# VOX_V847.net
KiCad netlist of a schematic drawn in EAGLE
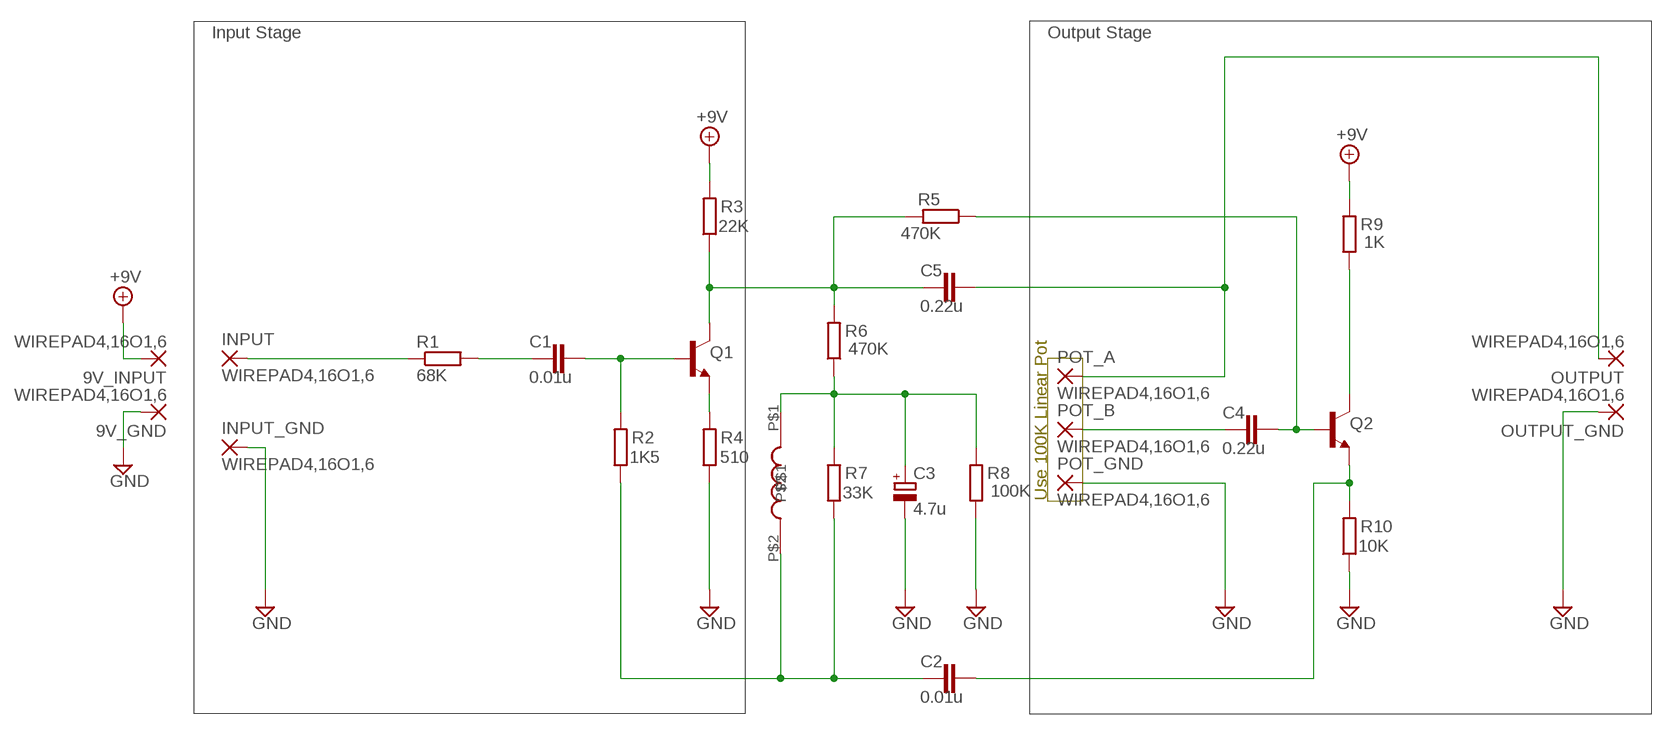
[diagram p0: schematic, sheet 1]

(export (version "E")
  (design (tool "Eeschema 10.0.6"))
  (components
    (comp (ref "9V_GND")
      (value "WIREPAD4,16O1,6")
      (footprint "eagle-import:4,16O1,6")
      (libsource (lib "eagle-import") (part "WIREPAD4,16O1,6"))
    )
    (comp (ref "9V_INPUT")
      (value "WIREPAD4,16O1,6")
      (footprint "eagle-import:4,16O1,6")
      (libsource (lib "eagle-import") (part "WIREPAD4,16O1,6"))
    )
    (comp (ref "C1")
      (value "0.01u")
      (footprint "eagle-import:C050-024X044")
      (libsource (lib "eagle-import") (part "C-EU050-024X044"))
    )
    (comp (ref "C2")
      (value "0.01u")
      (footprint "eagle-import:C050-024X044")
      (libsource (lib "eagle-import") (part "C-EU050-024X044"))
    )
    (comp (ref "C3")
      (value "4.7u")
      (footprint "eagle-import:E5-5")
      (libsource (lib "eagle-import") (part "CPOL-EUE5-5"))
    )
    (comp (ref "C4")
      (value "0.22u")
      (footprint "eagle-import:C075-042X103")
      (libsource (lib "eagle-import") (part "C-EU075-042X103"))
    )
    (comp (ref "C5")
      (value "0.22u")
      (footprint "eagle-import:C050-024X044")
      (libsource (lib "eagle-import") (part "C-EU050-024X044"))
    )
    (comp (ref "INPUT")
      (value "WIREPAD4,16O1,6")
      (footprint "eagle-import:4,16O1,6")
      (libsource (lib "eagle-import") (part "WIREPAD4,16O1,6"))
    )
    (comp (ref "INPUT_GND")
      (value "WIREPAD4,16O1,6")
      (footprint "eagle-import:4,16O1,6")
      (libsource (lib "eagle-import") (part "WIREPAD4,16O1,6"))
    )
    (comp (ref "OUTPUT")
      (value "WIREPAD4,16O1,6")
      (footprint "eagle-import:4,16O1,6")
      (libsource (lib "eagle-import") (part "WIREPAD4,16O1,6"))
    )
    (comp (ref "OUTPUT_GND")
      (value "WIREPAD4,16O1,6")
      (footprint "eagle-import:4,16O1,6")
      (libsource (lib "eagle-import") (part "WIREPAD4,16O1,6"))
    )
    (comp (ref "POT_A")
      (value "WIREPAD4,16O1,6")
      (footprint "eagle-import:4,16O1,6")
      (libsource (lib "eagle-import") (part "WIREPAD4,16O1,6"))
    )
    (comp (ref "POT_B")
      (value "WIREPAD4,16O1,6")
      (footprint "eagle-import:4,16O1,6")
      (libsource (lib "eagle-import") (part "WIREPAD4,16O1,6"))
    )
    (comp (ref "POT_GND")
      (value "WIREPAD4,16O1,6")
      (footprint "eagle-import:4,16O1,6")
      (libsource (lib "eagle-import") (part "WIREPAD4,16O1,6"))
    )
    (comp (ref "Q1")
      (value "MPSA18-NPN-TO92-EBC")
      (footprint "eagle-import:TO92-EBC")
      (libsource (lib "eagle-import") (part "-NPN-TO92-EBCMPSA18"))
    )
    (comp (ref "Q2")
      (value "MPSA18-NPN-TO92-EBC")
      (footprint "eagle-import:TO92-EBC")
      (libsource (lib "eagle-import") (part "-NPN-TO92-EBCMPSA18"))
    )
    (comp (ref "R1")
      (value "68K")
      (footprint "eagle-import:0207_7")
      (libsource (lib "eagle-import") (part "R-EU_0207/7"))
    )
    (comp (ref "R2")
      (value "1K5")
      (footprint "eagle-import:0207_12")
      (libsource (lib "eagle-import") (part "R-EU_0207/12"))
    )
    (comp (ref "R3")
      (value "22K")
      (footprint "eagle-import:0207_7")
      (libsource (lib "eagle-import") (part "R-EU_0207/7"))
    )
    (comp (ref "R4")
      (value "510")
      (footprint "eagle-import:0207_10")
      (libsource (lib "eagle-import") (part "R-EU_0207/10"))
    )
    (comp (ref "R5")
      (value "470K")
      (footprint "eagle-import:0207_7")
      (libsource (lib "eagle-import") (part "R-EU_0207/7"))
    )
    (comp (ref "R6")
      (value "470K")
      (footprint "eagle-import:0207_7")
      (libsource (lib "eagle-import") (part "R-EU_0207/7"))
    )
    (comp (ref "R7")
      (value "33K")
      (footprint "eagle-import:0207_7")
      (libsource (lib "eagle-import") (part "R-EU_0207/7"))
    )
    (comp (ref "R8")
      (value "100K")
      (footprint "eagle-import:0207_7")
      (libsource (lib "eagle-import") (part "R-EU_0207/7"))
    )
    (comp (ref "R9")
      (value "1K")
      (footprint "eagle-import:0207_12")
      (libsource (lib "eagle-import") (part "R-EU_0207/12"))
    )
    (comp (ref "R10")
      (value "10K")
      (footprint "eagle-import:0207_7")
      (libsource (lib "eagle-import") (part "R-EU_0207/7"))
    )
    (comp (ref "U$1")
      (value "FL01Y")
      (footprint "eagle-import:FL01Y")
      (libsource (lib "eagle-import") (part "FL01Y"))
    )
  )
  (nets
    (net (code "1") (name "+9V") (class "Default")
      (node (ref "9V_INPUT") (pin "1") (pinfunction "P_1") (pintype "passive"))
      (node (ref "R3") (pin "2") (pinfunction "2_2") (pintype "passive"))
      (node (ref "R9") (pin "2") (pinfunction "2_2") (pintype "passive"))
    )
    (net (code "2") (name "GND") (class "Default")
      (node (ref "9V_GND") (pin "1") (pinfunction "P_1") (pintype "passive"))
      (node (ref "C3") (pin "-") (pinfunction "-_-") (pintype "passive"))
      (node (ref "INPUT_GND") (pin "1") (pinfunction "P_1") (pintype "passive"))
      (node (ref "OUTPUT_GND") (pin "1") (pinfunction "P_1") (pintype "passive"))
      (node (ref "POT_GND") (pin "1") (pinfunction "P_1") (pintype "passive"))
      (node (ref "R10") (pin "1") (pinfunction "1_1") (pintype "passive"))
      (node (ref "R4") (pin "1") (pinfunction "1_1") (pintype "passive"))
      (node (ref "R8") (pin "1") (pinfunction "1_1") (pintype "passive"))
    )
    (net (code "3") (name "Net-(C1-Pad1)") (class "Default")
      (node (ref "C1") (pin "1") (pinfunction "1_1") (pintype "passive"))
      (node (ref "R1") (pin "2") (pinfunction "2_2") (pintype "passive"))
    )
    (net (code "4") (name "Net-(C1-Pad2)") (class "Default")
      (node (ref "C1") (pin "2") (pinfunction "2_2") (pintype "passive"))
      (node (ref "Q1") (pin "B") (pinfunction "B_B") (pintype "passive"))
      (node (ref "R2") (pin "2") (pinfunction "2_2") (pintype "passive"))
    )
    (net (code "5") (name "Net-(C2-Pad1)") (class "Default")
      (node (ref "C2") (pin "1") (pinfunction "1_1") (pintype "passive"))
      (node (ref "R2") (pin "1") (pinfunction "1_1") (pintype "passive"))
      (node (ref "R7") (pin "1") (pinfunction "1_1") (pintype "passive"))
      (node (ref "U$1") (pin "P$2") (pinfunction "P$2_P$2") (pintype "bidirectional"))
    )
    (net (code "6") (name "Net-(C2-Pad2)") (class "Default")
      (node (ref "C2") (pin "2") (pinfunction "2_2") (pintype "passive"))
      (node (ref "Q2") (pin "E") (pinfunction "E_E") (pintype "passive"))
      (node (ref "R10") (pin "2") (pinfunction "2_2") (pintype "passive"))
    )
    (net (code "7") (name "Net-(C3-Pad+)") (class "Default")
      (node (ref "C3") (pin "+") (pinfunction "+_+") (pintype "passive"))
      (node (ref "R6") (pin "1") (pinfunction "1_1") (pintype "passive"))
      (node (ref "R7") (pin "2") (pinfunction "2_2") (pintype "passive"))
      (node (ref "R8") (pin "2") (pinfunction "2_2") (pintype "passive"))
      (node (ref "U$1") (pin "P$1") (pinfunction "P$1_P$1") (pintype "bidirectional"))
    )
    (net (code "8") (name "Net-(C4-Pad2)") (class "Default")
      (node (ref "C4") (pin "2") (pinfunction "2_2") (pintype "passive"))
      (node (ref "Q2") (pin "B") (pinfunction "B_B") (pintype "passive"))
      (node (ref "R5") (pin "1") (pinfunction "1_1") (pintype "passive"))
    )
    (net (code "9") (name "Net-(C5-Pad1)") (class "Default")
      (node (ref "C5") (pin "1") (pinfunction "1_1") (pintype "passive"))
      (node (ref "Q1") (pin "C") (pinfunction "C_C") (pintype "passive"))
      (node (ref "R3") (pin "1") (pinfunction "1_1") (pintype "passive"))
      (node (ref "R5") (pin "2") (pinfunction "2_2") (pintype "passive"))
      (node (ref "R6") (pin "2") (pinfunction "2_2") (pintype "passive"))
    )
    (net (code "10") (name "Net-(INPUT-P)") (class "Default")
      (node (ref "INPUT") (pin "1") (pinfunction "P_1") (pintype "passive"))
      (node (ref "R1") (pin "1") (pinfunction "1_1") (pintype "passive"))
    )
    (net (code "11") (name "Net-(OUTPUT-P)") (class "Default")
      (node (ref "C5") (pin "2") (pinfunction "2_2") (pintype "passive"))
      (node (ref "OUTPUT") (pin "1") (pinfunction "P_1") (pintype "passive"))
      (node (ref "POT_A") (pin "1") (pinfunction "P_1") (pintype "passive"))
    )
    (net (code "12") (name "Net-(POT_B-P)") (class "Default")
      (node (ref "C4") (pin "1") (pinfunction "1_1") (pintype "passive"))
      (node (ref "POT_B") (pin "1") (pinfunction "P_1") (pintype "passive"))
    )
    (net (code "13") (name "Net-(Q1-PadE)") (class "Default")
      (node (ref "Q1") (pin "E") (pinfunction "E_E") (pintype "passive"))
      (node (ref "R4") (pin "2") (pinfunction "2_2") (pintype "passive"))
    )
    (net (code "14") (name "Net-(Q2-PadC)") (class "Default")
      (node (ref "Q2") (pin "C") (pinfunction "C_C") (pintype "passive"))
      (node (ref "R9") (pin "1") (pinfunction "1_1") (pintype "passive"))
    )
  )
)
